# RGBWW.net
KiCad netlist of a schematic drawn in EAGLE
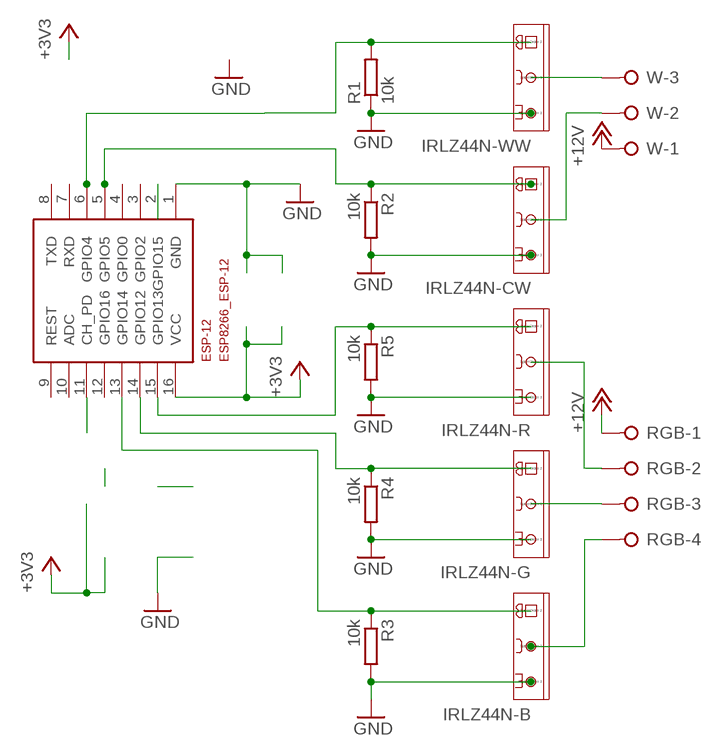
[diagram p0: schematic, sheet 1]

(export (version "E")
  (design (tool "Eeschema 10.0.6"))
  (components
    (comp (ref "ESP-12")
      (value "ESP8266_ESP-12")
      (footprint "eagle-import:ESP8266-ESP12")
      (libsource (lib "eagle-import") (part "ESP8266_ESP-12"))
    )
    (comp (ref "IRLZ44N-B")
      (value "TIP121")
      (footprint "eagle-import:TO220AV")
      (libsource (lib "eagle-import") (part "TIP121"))
    )
    (comp (ref "IRLZ44N-CW")
      (value "TIP121")
      (footprint "eagle-import:TO220AV")
      (libsource (lib "eagle-import") (part "TIP121"))
    )
    (comp (ref "IRLZ44N-G")
      (value "TIP121")
      (footprint "eagle-import:TO220AV")
      (libsource (lib "eagle-import") (part "TIP121"))
    )
    (comp (ref "IRLZ44N-R")
      (value "TIP121")
      (footprint "eagle-import:TO220AV")
      (libsource (lib "eagle-import") (part "TIP121"))
    )
    (comp (ref "IRLZ44N-WW")
      (value "TIP121")
      (footprint "eagle-import:TO220AV")
      (libsource (lib "eagle-import") (part "TIP121"))
    )
    (comp (ref "R1")
      (value "10k")
      (footprint "eagle-import:R0805")
      (libsource (lib "eagle-import") (part "R-EU_R0805"))
    )
    (comp (ref "R2")
      (value "10k")
      (footprint "eagle-import:R0805")
      (libsource (lib "eagle-import") (part "R-EU_R0805"))
    )
    (comp (ref "R3")
      (value "10k")
      (footprint "eagle-import:R0805")
      (libsource (lib "eagle-import") (part "R-EU_R0805"))
    )
    (comp (ref "R4")
      (value "10k")
      (footprint "eagle-import:R0805")
      (libsource (lib "eagle-import") (part "R-EU_R0805"))
    )
    (comp (ref "R5")
      (value "10k")
      (footprint "eagle-import:R0805")
      (libsource (lib "eagle-import") (part "R-EU_R0805"))
    )
    (comp (ref "RGB")
      (value "W237-04P")
      (footprint "eagle-import:W237-4P")
      (libsource (lib "eagle-import") (part "W237-04P"))
    )
    (comp (ref "W")
      (value "W237-03P")
      (footprint "eagle-import:W237-133")
      (libsource (lib "eagle-import") (part "W237-03P"))
    )
  )
  (nets
    (net (code "1") (name "+3V3") (class "Default")
      (node (ref "ESP-12") (pin "16") (pinfunction "VCC_16") (pintype "bidirectional"))
    )
    (net (code "2") (name "+12V") (class "Default")
      (node (ref "RGB") (pin "1") (pinfunction "KL_1") (pintype "passive"))
      (node (ref "W") (pin "1") (pinfunction "KL_1") (pintype "passive"))
    )
    (net (code "3") (name "GND") (class "Default")
      (node (ref "ESP-12") (pin "1") (pinfunction "GND_1") (pintype "bidirectional"))
      (node (ref "IRLZ44N-B") (pin "E") (pinfunction "E_E") (pintype "passive"))
      (node (ref "IRLZ44N-CW") (pin "E") (pinfunction "E_E") (pintype "passive"))
      (node (ref "IRLZ44N-G") (pin "E") (pinfunction "E_E") (pintype "passive"))
      (node (ref "IRLZ44N-R") (pin "E") (pinfunction "E_E") (pintype "passive"))
      (node (ref "IRLZ44N-WW") (pin "E") (pinfunction "E_E") (pintype "passive"))
      (node (ref "R1") (pin "1") (pinfunction "1_1") (pintype "passive"))
      (node (ref "R2") (pin "2") (pinfunction "2_2") (pintype "passive"))
      (node (ref "R3") (pin "2") (pinfunction "2_2") (pintype "passive"))
      (node (ref "R4") (pin "2") (pinfunction "2_2") (pintype "passive"))
      (node (ref "R5") (pin "2") (pinfunction "2_2") (pintype "passive"))
    )
    (net (code "4") (name "Net-(ESP-12-GPIO4)") (class "Default")
      (node (ref "ESP-12") (pin "6") (pinfunction "GPIO4_6") (pintype "bidirectional"))
      (node (ref "IRLZ44N-WW") (pin "B") (pinfunction "B_B") (pintype "passive"))
      (node (ref "R1") (pin "2") (pinfunction "2_2") (pintype "passive"))
    )
    (net (code "5") (name "Net-(ESP-12-GPIO5)") (class "Default")
      (node (ref "ESP-12") (pin "5") (pinfunction "GPIO5_5") (pintype "bidirectional"))
      (node (ref "IRLZ44N-CW") (pin "B") (pinfunction "B_B") (pintype "passive"))
      (node (ref "R2") (pin "1") (pinfunction "1_1") (pintype "passive"))
    )
    (net (code "6") (name "Net-(ESP-12-GPIO12)") (class "Default")
      (node (ref "ESP-12") (pin "14") (pinfunction "GPIO12_14") (pintype "bidirectional"))
      (node (ref "IRLZ44N-G") (pin "B") (pinfunction "B_B") (pintype "passive"))
      (node (ref "R4") (pin "1") (pinfunction "1_1") (pintype "passive"))
    )
    (net (code "7") (name "Net-(ESP-12-GPIO13)") (class "Default")
      (node (ref "ESP-12") (pin "15") (pinfunction "GPIO13_15") (pintype "bidirectional"))
      (node (ref "IRLZ44N-R") (pin "B") (pinfunction "B_B") (pintype "passive"))
      (node (ref "R5") (pin "1") (pinfunction "1_1") (pintype "passive"))
    )
    (net (code "8") (name "Net-(ESP-12-GPIO14)") (class "Default")
      (node (ref "ESP-12") (pin "13") (pinfunction "GPIO14_13") (pintype "bidirectional"))
      (node (ref "IRLZ44N-B") (pin "B") (pinfunction "B_B") (pintype "passive"))
      (node (ref "R3") (pin "1") (pinfunction "1_1") (pintype "passive"))
    )
    (net (code "9") (name "Net-(RGBB-KL)") (class "Default")
      (node (ref "IRLZ44N-R") (pin "C") (pinfunction "C_C") (pintype "passive"))
      (node (ref "RGB") (pin "2") (pinfunction "KL_2") (pintype "passive"))
    )
    (net (code "10") (name "Net-(RGBC-KL)") (class "Default")
      (node (ref "IRLZ44N-G") (pin "C") (pinfunction "C_C") (pintype "passive"))
      (node (ref "RGB") (pin "3") (pinfunction "KL_3") (pintype "passive"))
    )
    (net (code "11") (name "Net-(RGBD-KL)") (class "Default")
      (node (ref "IRLZ44N-B") (pin "C") (pinfunction "C_C") (pintype "passive"))
      (node (ref "RGB") (pin "4") (pinfunction "KL_4") (pintype "passive"))
    )
    (net (code "12") (name "Net-(WB-KL)") (class "Default")
      (node (ref "IRLZ44N-CW") (pin "C") (pinfunction "C_C") (pintype "passive"))
      (node (ref "W") (pin "2") (pinfunction "KL_2") (pintype "passive"))
    )
    (net (code "13") (name "Net-(WC-KL)") (class "Default")
      (node (ref "IRLZ44N-WW") (pin "C") (pinfunction "C_C") (pintype "passive"))
      (node (ref "W") (pin "3") (pinfunction "KL_3") (pintype "passive"))
    )
    (net (code "14") (name "unconnected-(ESP-12-ADC-Pad10)") (class "Default")
      (node (ref "ESP-12") (pin "10") (pinfunction "ADC_10") (pintype "bidirectional"))
    )
    (net (code "15") (name "unconnected-(ESP-12-CH_PD-Pad11)") (class "Default")
      (node (ref "ESP-12") (pin "11") (pinfunction "CH_PD_11") (pintype "bidirectional"))
    )
    (net (code "16") (name "unconnected-(ESP-12-GPIO0-Pad4)") (class "Default")
      (node (ref "ESP-12") (pin "4") (pinfunction "GPIO0_4") (pintype "bidirectional"))
    )
    (net (code "17") (name "unconnected-(ESP-12-GPIO2-Pad3)") (class "Default")
      (node (ref "ESP-12") (pin "3") (pinfunction "GPIO2_3") (pintype "bidirectional"))
    )
    (net (code "18") (name "unconnected-(ESP-12-GPIO15-Pad2)") (class "Default")
      (node (ref "ESP-12") (pin "2") (pinfunction "GPIO15_2") (pintype "bidirectional"))
    )
    (net (code "19") (name "unconnected-(ESP-12-GPIO16-Pad12)") (class "Default")
      (node (ref "ESP-12") (pin "12") (pinfunction "GPIO16_12") (pintype "bidirectional"))
    )
    (net (code "20") (name "unconnected-(ESP-12-REST-Pad9)") (class "Default")
      (node (ref "ESP-12") (pin "9") (pinfunction "REST_9") (pintype "bidirectional"))
    )
    (net (code "21") (name "unconnected-(ESP-12-RXD-Pad7)") (class "Default")
      (node (ref "ESP-12") (pin "7") (pinfunction "RXD_7") (pintype "bidirectional"))
    )
    (net (code "22") (name "unconnected-(ESP-12-TXD-Pad8)") (class "Default")
      (node (ref "ESP-12") (pin "8") (pinfunction "TXD_8") (pintype "bidirectional"))
    )
  )
)
